# RFAMP.net
KiCad netlist of a schematic drawn in Altium Designer
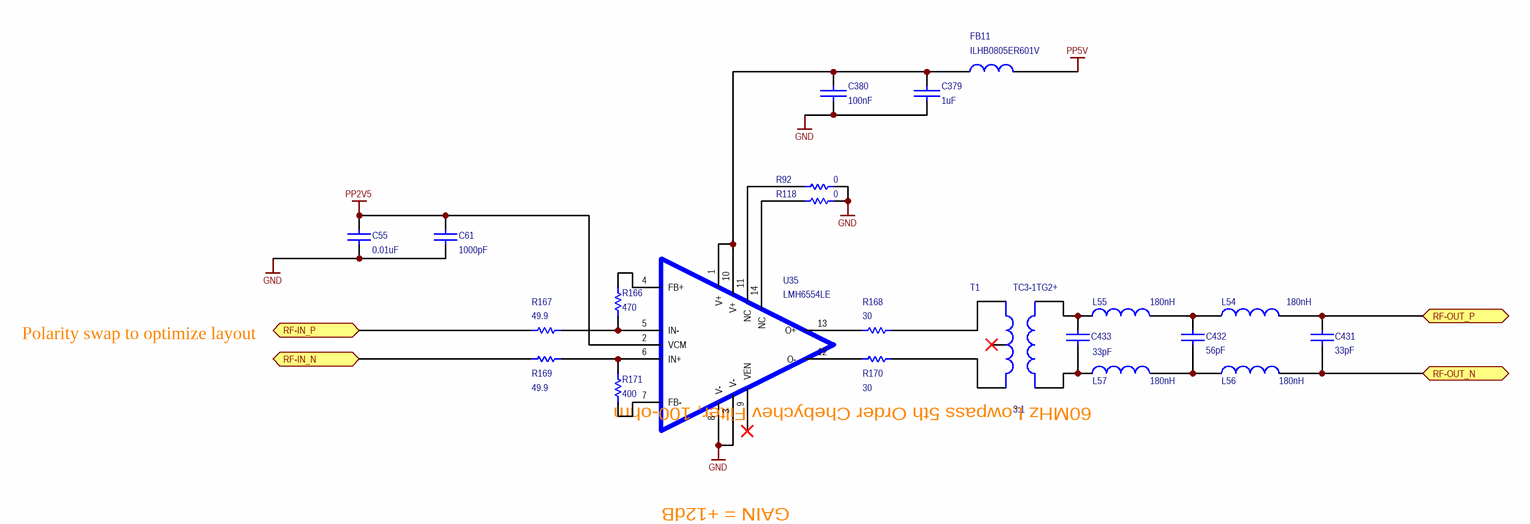
[diagram p0: RFAMP.SchDoc]

(export (version "E")
  (design (tool "Eeschema 10.0.6"))
  (components
    (comp (ref "C55")
      (value "0.01uF")
      (footprint "generic:0402")
      (description "CAP 0402")
      (fields (field (name "VOLTAGE") "25V") (field (name "MANUFACTURER") "Murata"))
      (libsource (lib "Graviton") (part "CAP 0402"))
    )
    (comp (ref "C61")
      (value "1000pF")
      (footprint "generic:0402")
      (description "CAP 0402")
      (fields (field (name "VOLTAGE") "50V") (field (name "MANUFACTURER") "Murata"))
      (libsource (lib "Graviton") (part "CAP 0402"))
    )
    (comp (ref "C379")
      (value "1uF")
      (footprint "generic:0402")
      (description "Ceramic Capacitor SMD")
      (fields (field (name "MANUFACTURER") "Murata") (field (name "Comment") "GRM155R61A105KE15D"))
      (libsource (lib "*") (part "CAP"))
    )
    (comp (ref "C380")
      (value "100nF")
      (footprint "generic:0402")
      (description "Ceramic Capacitor SMD")
      (fields (field (name "MANUFACTURER") "Murata") (field (name "VOLTAGE") "16V"))
      (libsource (lib "*") (part "CAP"))
    )
    (comp (ref "C431")
      (value "33pF")
      (footprint "generic:0402")
      (description "CAP 0402")
      (fields (field (name "VOLTAGE") "50V") (field (name "MANUFACTURER") "Murata"))
      (libsource (lib "Graviton") (part "CAP 0402"))
    )
    (comp (ref "C432")
      (value "56pF")
      (footprint "generic:0402")
      (description "CAP 0402")
      (fields (field (name "VOLTAGE") "50V") (field (name "MANUFACTURER") "Murata"))
      (libsource (lib "Graviton") (part "CAP 0402"))
    )
    (comp (ref "C433")
      (value "33pF")
      (footprint "generic:0402")
      (description "CAP 0402")
      (fields (field (name "VOLTAGE") "50V") (field (name "MANUFACTURER") "Murata"))
      (libsource (lib "Graviton") (part "CAP 0402"))
    )
    (comp (ref "FB11")
      (value "ILHB0805ER601V")
      (footprint "0805")
      (description "Ferrite Bead 600-Ohm @ 100MHz 0805")
      (fields (field (name "MANUFACTURER") "Vishay Dale"))
      (libsource (lib "*") (part "INDUCTANCE1"))
    )
    (comp (ref "L54")
      (value "180nH")
      (footprint "0603")
      (description "Inductor Wirewound Air 91nH +/-2% SMD 0402")
      (fields (field (name "MANUFACTURER") "Murata") (field (name "Comment") "LQW18ANR18G00D"))
      (libsource (lib "generic") (part "INDUCTOR"))
    )
    (comp (ref "L55")
      (value "180nH")
      (footprint "0603")
      (description "Inductor Wirewound Air 91nH +/-2% SMD 0402")
      (fields (field (name "MANUFACTURER") "Murata") (field (name "Comment") "LQW18ANR18G00D"))
      (libsource (lib "generic") (part "INDUCTOR"))
    )
    (comp (ref "L56")
      (value "180nH")
      (footprint "0603")
      (description "Inductor Wirewound Air 91nH +/-2% SMD 0402")
      (fields (field (name "MANUFACTURER") "Murata") (field (name "Comment") "LQW18ANR18G00D"))
      (libsource (lib "generic") (part "INDUCTOR"))
    )
    (comp (ref "L57")
      (value "180nH")
      (footprint "0603")
      (description "Inductor Wirewound Air 91nH +/-2% SMD 0402")
      (fields (field (name "MANUFACTURER") "Murata") (field (name "Comment") "LQW18ANR18G00D"))
      (libsource (lib "generic") (part "INDUCTOR"))
    )
    (comp (ref "R92")
      (value "0")
      (footprint "generic:0402")
      (description "Resistor, SMD 0402")
      (fields (field (name "MANUFACTURER") "Panasonic") (field (name "Comment") "ERJ-2GE0R00X"))
      (libsource (lib "generic") (part "RES 0402"))
    )
    (comp (ref "R118")
      (value "0")
      (footprint "generic:0402")
      (description "Resistor, SMD 0402")
      (fields (field (name "MANUFACTURER") "Panasonic") (field (name "Comment") "ERJ-2GE0R00X"))
      (libsource (lib "generic") (part "RES 0402"))
    )
    (comp (ref "R166")
      (value "470")
      (footprint "generic:0402")
      (description "Resistor, SMD 0402")
      (fields (field (name "MANUFACTURER") "Panasonic") (field (name "TOLERANCE") "0.1%"))
      (libsource (lib "Graviton") (part "RES 0402"))
    )
    (comp (ref "R167")
      (value "49.9")
      (footprint "generic:0402")
      (description "Resistor, SMD 0402")
      (fields (field (name "MANUFACTURER") "Panasonic") (field (name "TOLERANCE") "0.1%"))
      (libsource (lib "Graviton") (part "RES 0402"))
    )
    (comp (ref "R168")
      (value "30")
      (footprint "generic:0402")
      (description "Resistor, SMD 0402")
      (fields (field (name "MANUFACTURER") "TE Connectivity") (field (name "TOLERANCE") "0.1%"))
      (libsource (lib "Graviton") (part "RES 0402"))
    )
    (comp (ref "R169")
      (value "49.9")
      (footprint "generic:0402")
      (description "Resistor, SMD 0402")
      (fields (field (name "MANUFACTURER") "Panasonic") (field (name "TOLERANCE") "0.1%"))
      (libsource (lib "Graviton") (part "RES 0402"))
    )
    (comp (ref "R170")
      (value "30")
      (footprint "generic:0402")
      (description "Resistor, SMD 0402")
      (fields (field (name "MANUFACTURER") "Panasonic") (field (name "TOLERANCE") "0.1%"))
      (libsource (lib "Graviton") (part "RES 0402"))
    )
    (comp (ref "R171")
      (value "400")
      (footprint "generic:0402")
      (description "Resistor, SMD 0402")
      (fields (field (name "MANUFACTURER") "Panasonic") (field (name "TOLERANCE") "0.1%"))
      (libsource (lib "Graviton") (part "RES 0402"))
    )
    (comp (ref "T1")
      (value "3:1")
      (footprint "AT224-1A")
      (description "RF Transformer 0.4 to 500MHz SMD")
      (fields
        (field (name "MANUFACTURER P/N") "TC3-1TG2+")
        (field (name "MANUFACTURER") "Mini-Circuits")
        (field (name "Comment") "TC3-1TG2+")
      )
      (libsource (lib "phase4") (part "TC1-1TG2+"))
    )
    (comp (ref "U35")
      (value "LMH6554LE")
      (footprint "texas_instruments:NHJ0014A")
      (description "2.8 GHz Ultra Linear Fully Differential Amplifier")
      (fields (field (name "MANUFACTURER") "Texas Instruments"))
      (libsource (lib "ti") (part "LMH6554LE"))
    )
  )
  (nets
    (net (code "1") (name "/RF-IN_N") (class "Default")
      (node (ref "R169") (pin "2") (pinfunction "2_2") (pintype "passive"))
    )
    (net (code "2") (name "/RF-IN_P") (class "Default")
      (node (ref "R167") (pin "2") (pinfunction "2_2") (pintype "passive"))
    )
    (net (code "3") (name "/RF-OUT_N") (class "Default")
      (node (ref "C431") (pin "1") (pinfunction "1_1") (pintype "passive"))
      (node (ref "L56") (pin "1") (pinfunction "1_1") (pintype "passive"))
    )
    (net (code "4") (name "/RF-OUT_P") (class "Default")
      (node (ref "C431") (pin "2") (pinfunction "2_2") (pintype "passive"))
      (node (ref "L54") (pin "1") (pinfunction "1_1") (pintype "passive"))
    )
    (net (code "5") (name "GND") (class "Default")
      (node (ref "C379") (pin "1") (pinfunction "1_1") (pintype "passive"))
      (node (ref "C380") (pin "1") (pinfunction "1_1") (pintype "passive"))
      (node (ref "C55") (pin "1") (pinfunction "1_1") (pintype "passive"))
      (node (ref "C61") (pin "1") (pinfunction "1_1") (pintype "passive"))
      (node (ref "R118") (pin "2") (pinfunction "2_2") (pintype "passive"))
      (node (ref "R92") (pin "2") (pinfunction "2_2") (pintype "passive"))
      (node (ref "U35") (pin "3") (pinfunction "V-_3") (pintype "passive"))
      (node (ref "U35") (pin "8") (pinfunction "V-_8") (pintype "passive"))
    )
    (net (code "6") (name "Net-(C379-Pad2)") (class "Default")
      (node (ref "C379") (pin "2") (pinfunction "2_2") (pintype "passive"))
      (node (ref "C380") (pin "2") (pinfunction "2_2") (pintype "passive"))
      (node (ref "FB11") (pin "1") (pinfunction "1_1") (pintype "passive"))
      (node (ref "U35") (pin "1") (pinfunction "V+_1") (pintype "passive"))
      (node (ref "U35") (pin "10") (pinfunction "V+_10") (pintype "passive"))
    )
    (net (code "7") (name "Net-(C432-Pad1)") (class "Default")
      (node (ref "C432") (pin "1") (pinfunction "1_1") (pintype "passive"))
      (node (ref "L56") (pin "2") (pinfunction "2_2") (pintype "passive"))
      (node (ref "L57") (pin "1") (pinfunction "1_1") (pintype "passive"))
    )
    (net (code "8") (name "Net-(C432-Pad2)") (class "Default")
      (node (ref "C432") (pin "2") (pinfunction "2_2") (pintype "passive"))
      (node (ref "L54") (pin "2") (pinfunction "2_2") (pintype "passive"))
      (node (ref "L55") (pin "1") (pinfunction "1_1") (pintype "passive"))
    )
    (net (code "9") (name "Net-(R92-Pad1)") (class "Default")
      (node (ref "R92") (pin "1") (pinfunction "1_1") (pintype "passive"))
      (node (ref "U35") (pin "11") (pinfunction "NC_11") (pintype "passive"))
    )
    (net (code "10") (name "Net-(R118-Pad1)") (class "Default")
      (node (ref "R118") (pin "1") (pinfunction "1_1") (pintype "passive"))
      (node (ref "U35") (pin "14") (pinfunction "NC_14") (pintype "passive"))
    )
    (net (code "11") (name "Net-(T1-Pri+)") (class "Default")
      (node (ref "C433") (pin "1") (pinfunction "1_1") (pintype "passive"))
      (node (ref "L57") (pin "2") (pinfunction "2_2") (pintype "passive"))
      (node (ref "T1") (pin "6") (pinfunction "Pri+_6") (pintype "passive"))
    )
    (net (code "12") (name "Net-(T1-Pri-)") (class "Default")
      (node (ref "C433") (pin "2") (pinfunction "2_2") (pintype "passive"))
      (node (ref "L55") (pin "2") (pinfunction "2_2") (pintype "passive"))
      (node (ref "T1") (pin "4") (pinfunction "Pri-_4") (pintype "passive"))
    )
    (net (code "13") (name "Net-(T1-Sec+)") (class "Default")
      (node (ref "R170") (pin "1") (pinfunction "1_1") (pintype "passive"))
      (node (ref "T1") (pin "1") (pinfunction "Sec+_1") (pintype "passive"))
    )
    (net (code "14") (name "Net-(T1-Sec-)") (class "Default")
      (node (ref "R168") (pin "1") (pinfunction "1_1") (pintype "passive"))
      (node (ref "T1") (pin "3") (pinfunction "Sec-_3") (pintype "passive"))
    )
    (net (code "15") (name "Net-(U35-FB+)") (class "Default")
      (node (ref "R166") (pin "1") (pinfunction "1_1") (pintype "passive"))
      (node (ref "U35") (pin "4") (pinfunction "FB+_4") (pintype "passive"))
    )
    (net (code "16") (name "Net-(U35-FB-)") (class "Default")
      (node (ref "R171") (pin "2") (pinfunction "2_2") (pintype "passive"))
      (node (ref "U35") (pin "7") (pinfunction "FB-_7") (pintype "passive"))
    )
    (net (code "17") (name "Net-(U35-IN+)") (class "Default")
      (node (ref "R169") (pin "1") (pinfunction "1_1") (pintype "passive"))
      (node (ref "R171") (pin "1") (pinfunction "1_1") (pintype "passive"))
      (node (ref "U35") (pin "6") (pinfunction "IN+_6") (pintype "passive"))
    )
    (net (code "18") (name "Net-(U35-IN-)") (class "Default")
      (node (ref "R166") (pin "2") (pinfunction "2_2") (pintype "passive"))
      (node (ref "R167") (pin "1") (pinfunction "1_1") (pintype "passive"))
      (node (ref "U35") (pin "5") (pinfunction "IN-_5") (pintype "passive"))
    )
    (net (code "19") (name "Net-(U35-O+)") (class "Default")
      (node (ref "R168") (pin "2") (pinfunction "2_2") (pintype "passive"))
      (node (ref "U35") (pin "13") (pinfunction "O+_13") (pintype "passive"))
    )
    (net (code "20") (name "Net-(U35-O-)") (class "Default")
      (node (ref "R170") (pin "2") (pinfunction "2_2") (pintype "passive"))
      (node (ref "U35") (pin "12") (pinfunction "O-_12") (pintype "passive"))
    )
    (net (code "21") (name "PP2V5") (class "Default")
      (node (ref "C55") (pin "2") (pinfunction "2_2") (pintype "passive"))
      (node (ref "C61") (pin "2") (pinfunction "2_2") (pintype "passive"))
      (node (ref "U35") (pin "2") (pinfunction "VCM_2") (pintype "passive"))
    )
    (net (code "22") (name "PP5V") (class "Default")
      (node (ref "FB11") (pin "2") (pinfunction "2_2") (pintype "passive"))
    )
    (net (code "23") (name "unconnected-(T1-SecCT-Pad2)") (class "Default")
      (node (ref "T1") (pin "2") (pinfunction "SecCT_2") (pintype "passive+no_connect"))
    )
    (net (code "24") (name "unconnected-(U35-VEN-Pad9)") (class "Default")
      (node (ref "U35") (pin "9") (pinfunction "VEN_9") (pintype "passive+no_connect"))
    )
  )
)
